# funcgen.net
KiCad netlist of a schematic drawn in Altium Designer
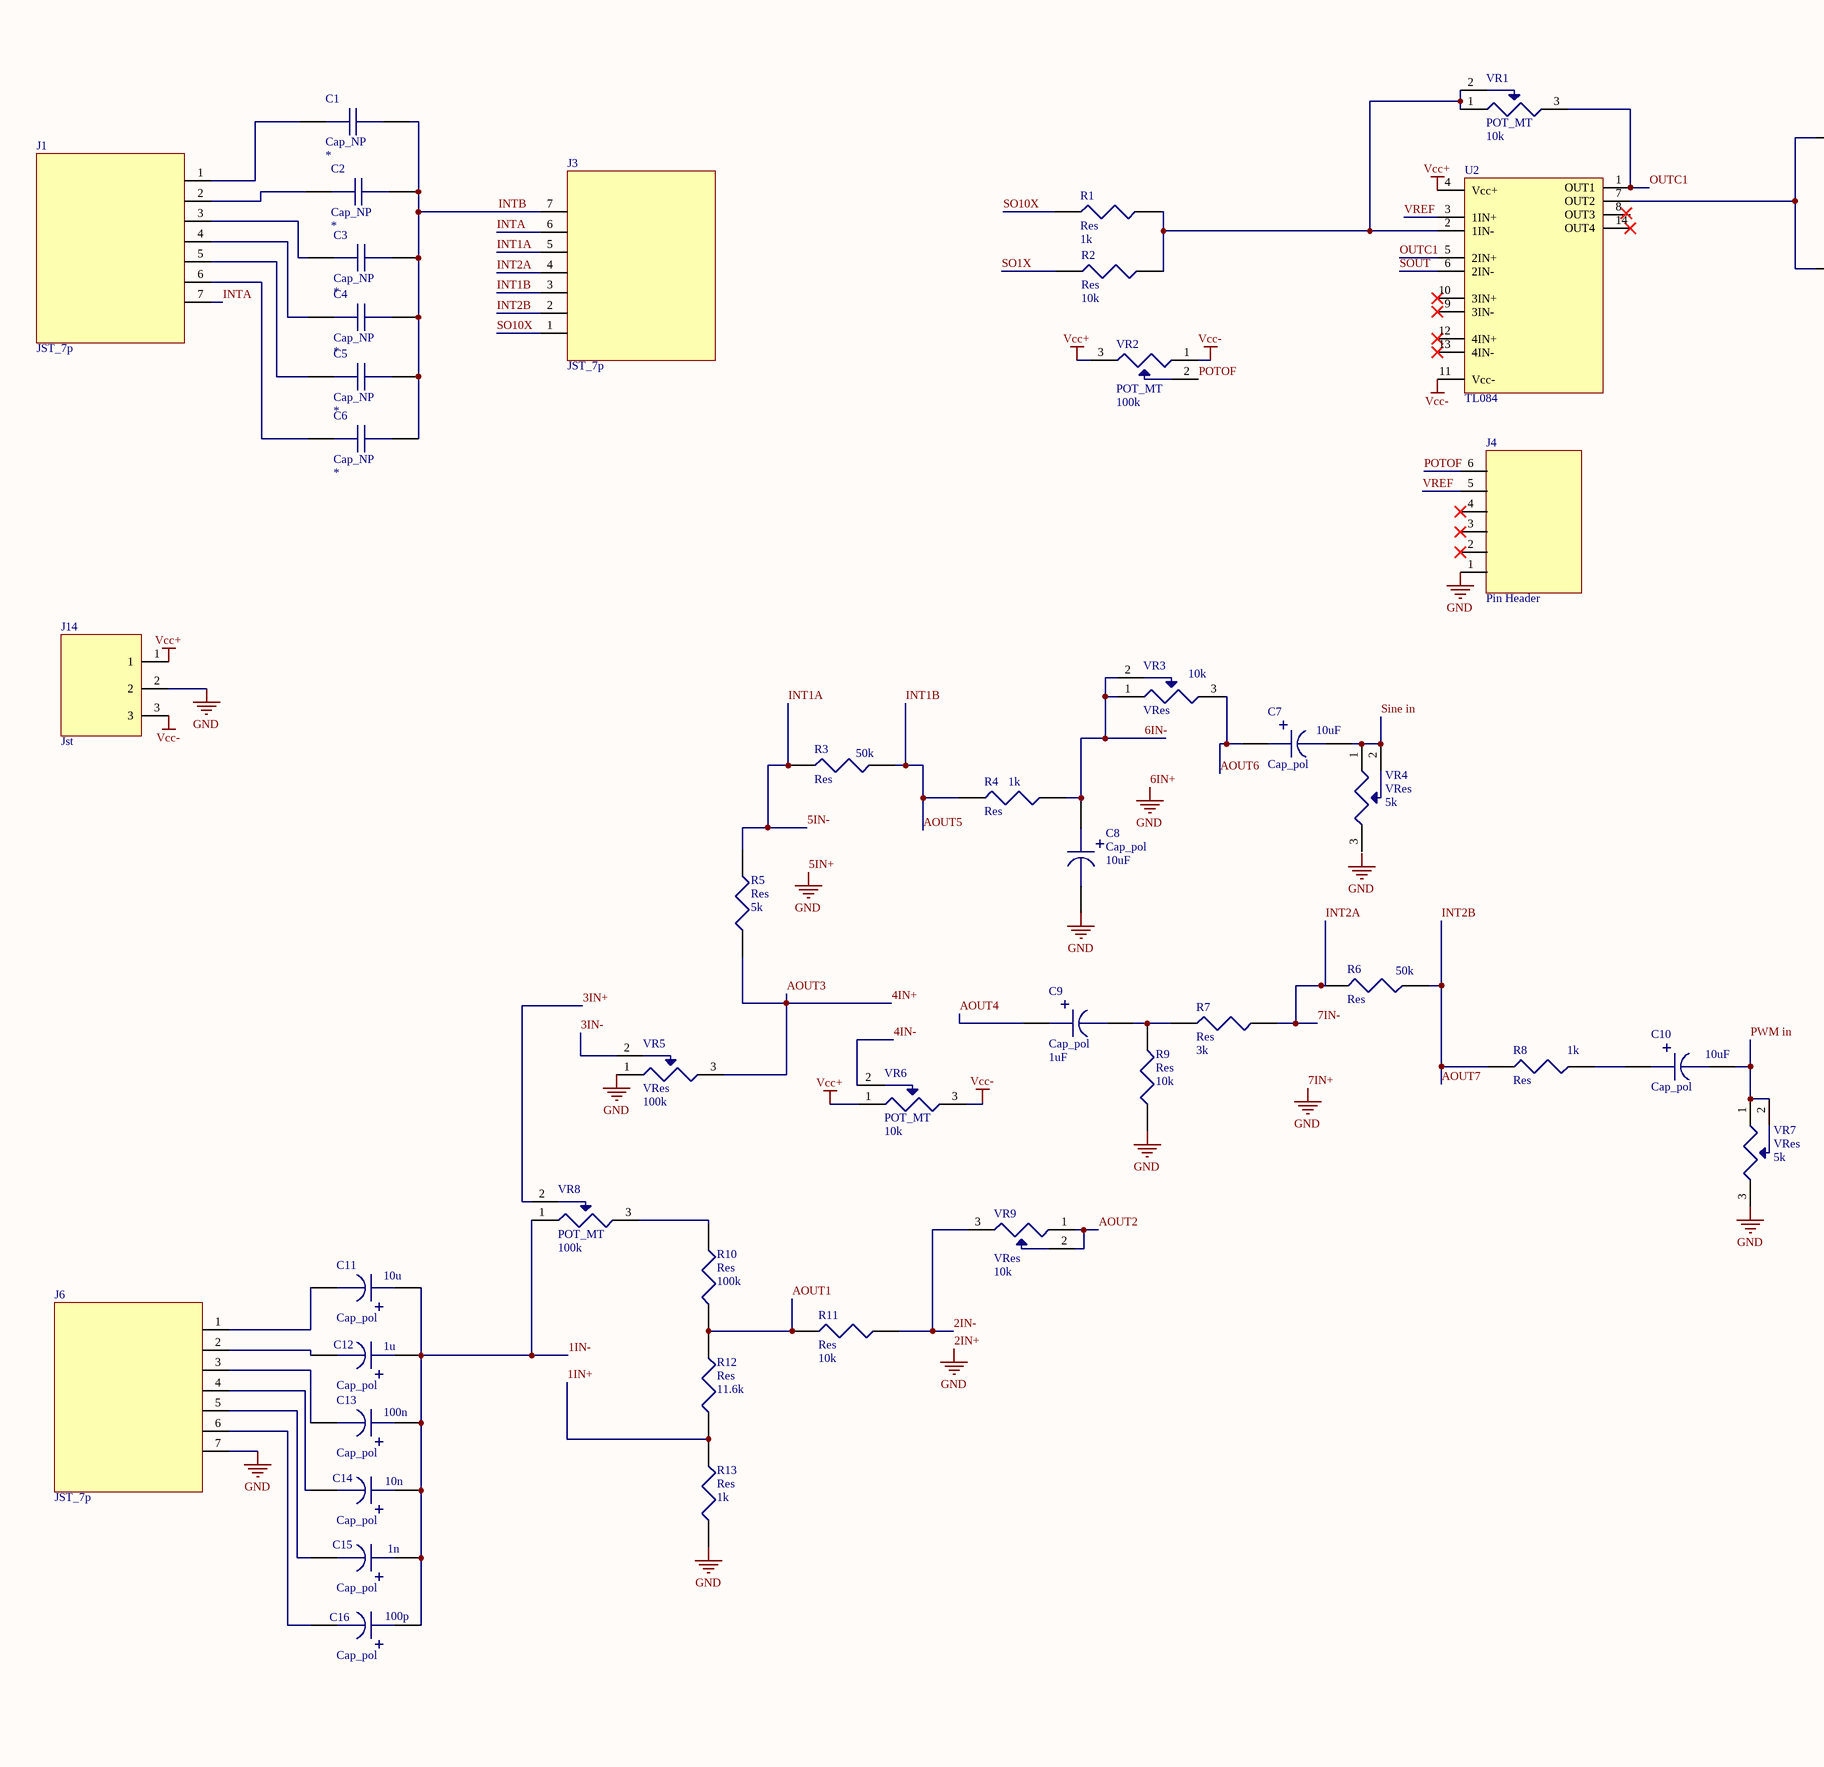
[diagram p0: funcgen.SchDoc, left]
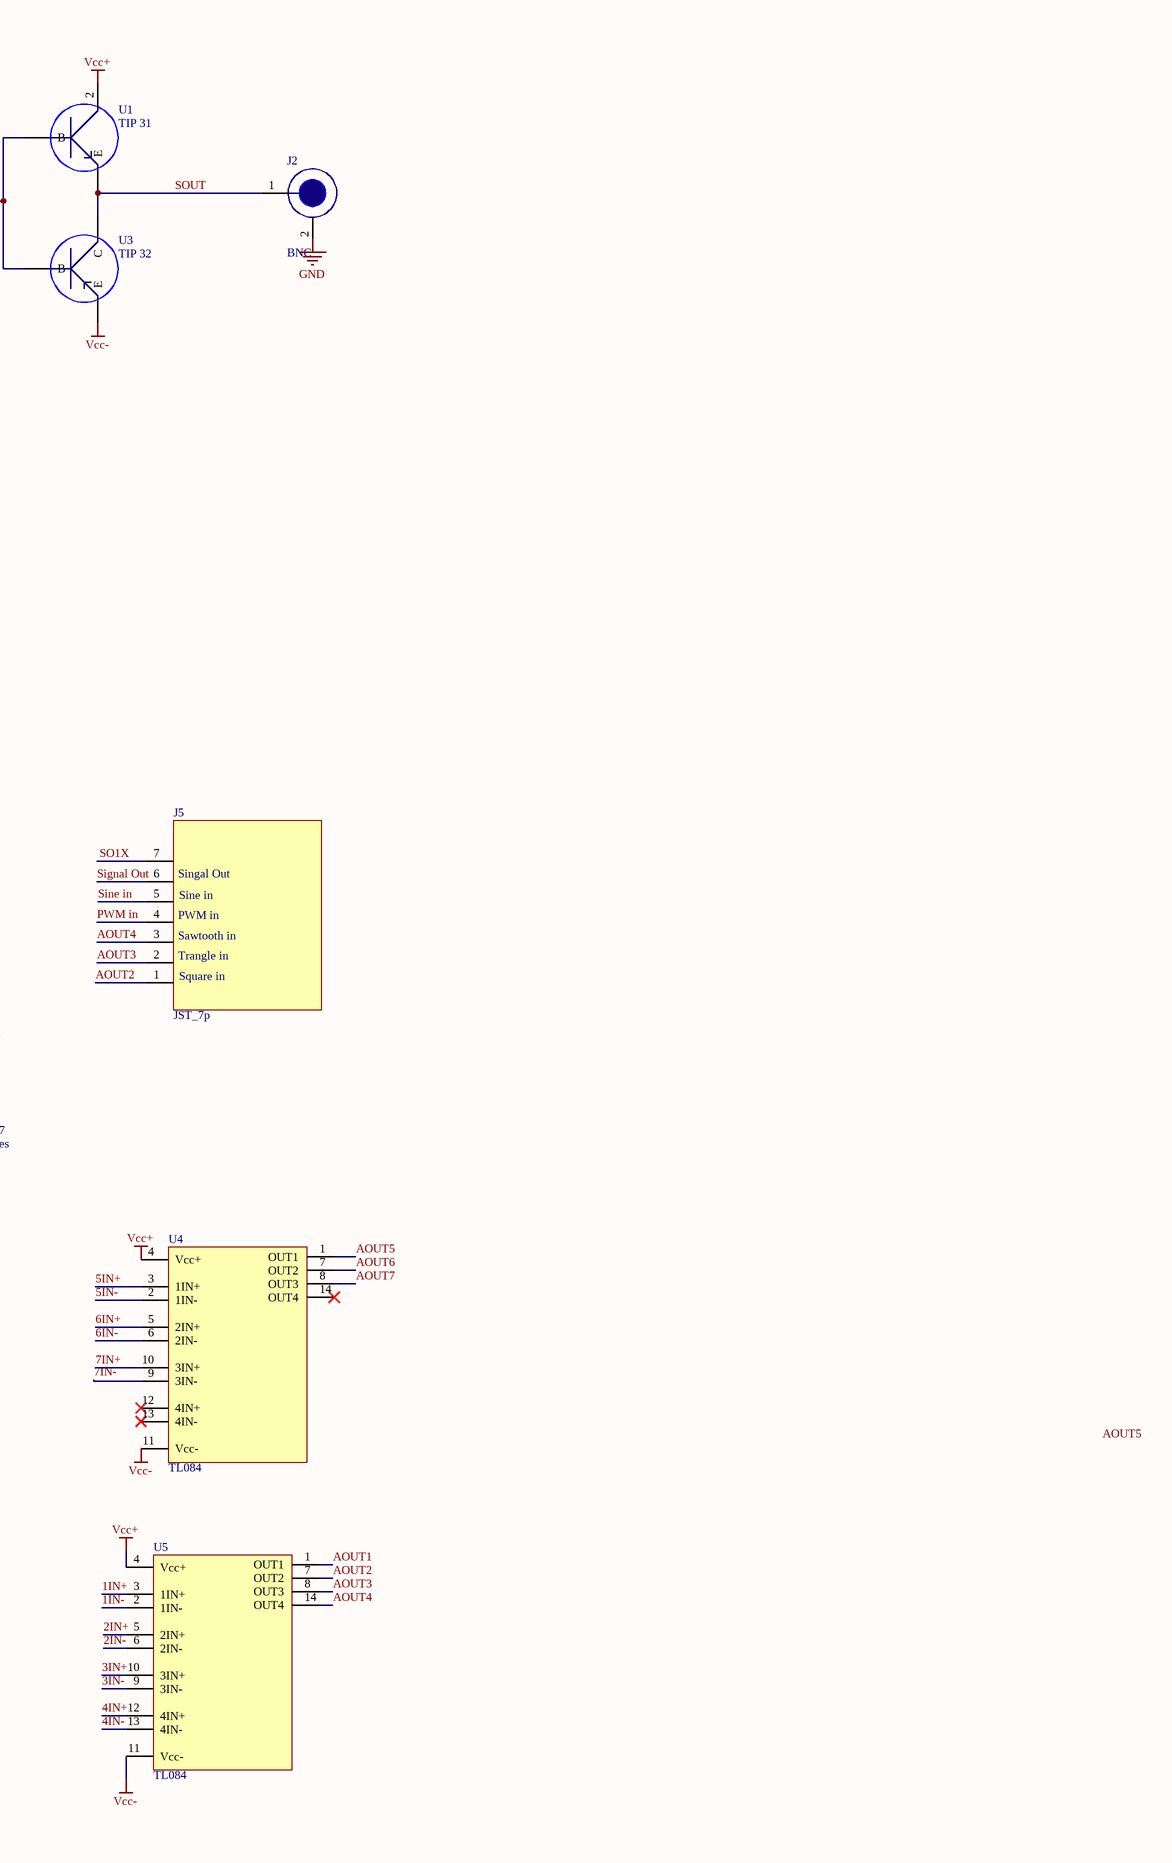
[diagram p1: funcgen.SchDoc, right]

(export (version "E")
  (design (tool "Eeschema 10.0.6"))
  (components
    (comp (ref "C1")
      (value "Cap_NP")
      (footprint "Cap NP")
      (fields (field (name "ALTIUM_VALUE") "*"))
      (libsource (lib "Funcgen") (part "Cap_NP"))
    )
    (comp (ref "C2")
      (value "Cap_NP")
      (footprint "Cap NP")
      (fields (field (name "ALTIUM_VALUE") "*"))
      (libsource (lib "Funcgen") (part "Cap_NP"))
    )
    (comp (ref "C3")
      (value "Cap_NP")
      (footprint "Cap NP")
      (fields (field (name "ALTIUM_VALUE") "*"))
      (libsource (lib "Funcgen") (part "Cap_NP"))
    )
    (comp (ref "C4")
      (value "Cap_NP")
      (footprint "Cap NP")
      (fields (field (name "ALTIUM_VALUE") "*"))
      (libsource (lib "Funcgen") (part "Cap_NP"))
    )
    (comp (ref "C5")
      (value "Cap_NP")
      (footprint "Cap NP")
      (fields (field (name "ALTIUM_VALUE") "*"))
      (libsource (lib "Funcgen") (part "Cap_NP"))
    )
    (comp (ref "C6")
      (value "Cap_NP")
      (footprint "Cap NP")
      (fields (field (name "ALTIUM_VALUE") "*"))
      (libsource (lib "Funcgen") (part "Cap_NP"))
    )
    (comp (ref "C7")
      (value "Cap_pol")
      (footprint "Cap pol")
      (fields (field (name "ALTIUM_VALUE") "10uF"))
      (libsource (lib "Schlib1") (part "Cap_pol"))
    )
    (comp (ref "C8")
      (value "Cap_pol")
      (footprint "Cap pol")
      (fields (field (name "ALTIUM_VALUE") "10uF"))
      (libsource (lib "Schlib1") (part "Cap_pol"))
    )
    (comp (ref "C9")
      (value "Cap_pol")
      (footprint "Cap pol")
      (fields (field (name "ALTIUM_VALUE") "1uF"))
      (libsource (lib "Schlib1") (part "Cap_pol"))
    )
    (comp (ref "C10")
      (value "Cap_pol")
      (footprint "Cap pol")
      (fields (field (name "ALTIUM_VALUE") "10uF"))
      (libsource (lib "Schlib1") (part "Cap_pol"))
    )
    (comp (ref "C11")
      (value "Cap_pol")
      (footprint "Cap pol")
      (fields (field (name "ALTIUM_VALUE") "10u"))
      (libsource (lib "Schlib1") (part "Cap_pol"))
    )
    (comp (ref "C12")
      (value "Cap_pol")
      (footprint "Cap pol")
      (fields (field (name "ALTIUM_VALUE") "1u"))
      (libsource (lib "Schlib1") (part "Cap_pol"))
    )
    (comp (ref "C13")
      (value "Cap_pol")
      (footprint "Cap pol")
      (fields (field (name "ALTIUM_VALUE") "100n"))
      (libsource (lib "Schlib1") (part "Cap_pol"))
    )
    (comp (ref "C14")
      (value "Cap_pol")
      (footprint "Cap pol")
      (fields (field (name "ALTIUM_VALUE") "10n"))
      (libsource (lib "Schlib1") (part "Cap_pol"))
    )
    (comp (ref "C15")
      (value "Cap_pol")
      (footprint "Cap pol")
      (fields (field (name "ALTIUM_VALUE") "1n"))
      (libsource (lib "Schlib1") (part "Cap_pol"))
    )
    (comp (ref "C16")
      (value "Cap_pol")
      (footprint "Cap pol")
      (fields (field (name "ALTIUM_VALUE") "100p"))
      (libsource (lib "Schlib1") (part "Cap_pol"))
    )
    (comp (ref "J1") (value "JST_7p") (footprint "JST_7p") (libsource (lib "Funcgen") (part "JST_7p")))
    (comp (ref "J2") (value "BNC") (footprint "PcbLib1:BNC") (libsource (lib "Funcgen") (part "BNC")))
    (comp (ref "J3") (value "JST_7p") (footprint "JST_7p") (libsource (lib "") (part "JST_7p_1")))
    (comp (ref "J4") (value "Pin Header") (footprint "JST_6p") (libsource (lib "Schlib1") (part "JST_6p")))
    (comp (ref "J5") (value "JST_7p") (footprint "JST_7p") (libsource (lib "") (part "JST_7p_1")))
    (comp (ref "J6") (value "JST_7p") (footprint "JST_7p") (libsource (lib "Funcgen") (part "JST_7p")))
    (comp (ref "J14") (value "Jst") (footprint "Funcgen:Jst_3p") (libsource (lib "Funcgen") (part "Jst_3p")))
    (comp (ref "R1")
      (value "Res")
      (footprint "Res")
      (fields (field (name "ALTIUM_VALUE") "1k"))
      (libsource (lib "Funcgen") (part "Res"))
    )
    (comp (ref "R2")
      (value "Res")
      (footprint "Res")
      (fields (field (name "ALTIUM_VALUE") "10k"))
      (libsource (lib "Funcgen") (part "Res"))
    )
    (comp (ref "R3")
      (value "Res")
      (footprint "Res")
      (fields (field (name "ALTIUM_VALUE") "50k"))
      (libsource (lib "Schlib1") (part "Res"))
    )
    (comp (ref "R4")
      (value "Res")
      (footprint "Res")
      (fields (field (name "ALTIUM_VALUE") "1k"))
      (libsource (lib "Schlib1") (part "Res"))
    )
    (comp (ref "R5")
      (value "Res")
      (footprint "Res")
      (fields (field (name "ALTIUM_VALUE") "5k"))
      (libsource (lib "Schlib1") (part "Res"))
    )
    (comp (ref "R6")
      (value "Res")
      (footprint "Res")
      (fields (field (name "ALTIUM_VALUE") "50k"))
      (libsource (lib "Schlib1") (part "Res"))
    )
    (comp (ref "R7")
      (value "Res")
      (footprint "Res")
      (fields (field (name "ALTIUM_VALUE") "3k"))
      (libsource (lib "Schlib1") (part "Res"))
    )
    (comp (ref "R8")
      (value "Res")
      (footprint "Res")
      (fields (field (name "ALTIUM_VALUE") "1k"))
      (libsource (lib "Schlib1") (part "Res"))
    )
    (comp (ref "R9")
      (value "Res")
      (footprint "Res")
      (fields (field (name "ALTIUM_VALUE") "10k"))
      (libsource (lib "Schlib1") (part "Res"))
    )
    (comp (ref "R10")
      (value "Res")
      (footprint "Res")
      (fields (field (name "ALTIUM_VALUE") "100k"))
      (libsource (lib "Schlib1") (part "Res"))
    )
    (comp (ref "R11")
      (value "Res")
      (footprint "Res")
      (fields (field (name "ALTIUM_VALUE") "10k"))
      (libsource (lib "Schlib1") (part "Res"))
    )
    (comp (ref "R12")
      (value "Res")
      (footprint "Res")
      (fields (field (name "ALTIUM_VALUE") "11.6k"))
      (libsource (lib "Schlib1") (part "Res"))
    )
    (comp (ref "R13")
      (value "Res")
      (footprint "Res")
      (fields (field (name "ALTIUM_VALUE") "1k"))
      (libsource (lib "Schlib1") (part "Res"))
    )
    (comp (ref "U1") (value "TIP 31") (footprint "TIP 31") (libsource (lib "Funcgen") (part "TIP 31")))
    (comp (ref "U2") (value "TL084") (footprint "TL084") (libsource (lib "Funcgen") (part "TL084")))
    (comp (ref "U3") (value "TIP 32") (footprint "TIP 31") (libsource (lib "Funcgen") (part "TIP 32")))
    (comp (ref "U4") (value "TL084") (footprint "TL084") (libsource (lib "Schlib1") (part "TL084")))
    (comp (ref "U5") (value "TL084") (footprint "TL084") (libsource (lib "Schlib1") (part "TL084")))
    (comp (ref "VR1")
      (value "POT_MT")
      (footprint "POT MT")
      (fields (field (name "ALTIUM_VALUE") "10k"))
      (libsource (lib "Funcgen") (part "POT_MT"))
    )
    (comp (ref "VR2")
      (value "POT_MT")
      (footprint "POT MT")
      (fields (field (name "ALTIUM_VALUE") "100k"))
      (libsource (lib "Funcgen") (part "POT_MT"))
    )
    (comp (ref "VR3")
      (value "VRes")
      (footprint "VerRes")
      (fields (field (name "ALTIUM_VALUE") "10k"))
      (libsource (lib "Schlib1") (part "VRes"))
    )
    (comp (ref "VR4")
      (value "VRes")
      (footprint "VerRes")
      (fields (field (name "ALTIUM_VALUE") "5k"))
      (libsource (lib "Schlib1") (part "VRes"))
    )
    (comp (ref "VR5")
      (value "VRes")
      (footprint "VerRes")
      (fields (field (name "ALTIUM_VALUE") "100k"))
      (libsource (lib "Schlib1") (part "VRes"))
    )
    (comp (ref "VR6")
      (value "POT_MT")
      (footprint "POT MT")
      (fields (field (name "ALTIUM_VALUE") "10k"))
      (libsource (lib "Schlib1") (part "POT_MT"))
    )
    (comp (ref "VR7")
      (value "VRes")
      (footprint "VerRes")
      (fields (field (name "ALTIUM_VALUE") "5k"))
      (libsource (lib "Schlib1") (part "VRes"))
    )
    (comp (ref "VR8")
      (value "POT_MT")
      (footprint "POT MT")
      (fields (field (name "ALTIUM_VALUE") "100k"))
      (libsource (lib "Schlib1") (part "POT_MT"))
    )
    (comp (ref "VR9")
      (value "VRes")
      (footprint "VerRes")
      (fields (field (name "ALTIUM_VALUE") "10k"))
      (libsource (lib "Schlib1") (part "VRes"))
    )
  )
  (nets
    (net (code "1") (name "/1IN+") (class "Default")
      (node (ref "R12") (pin "1") (pinfunction "1_1") (pintype "passive"))
      (node (ref "R13") (pin "2") (pinfunction "2_2") (pintype "passive"))
      (node (ref "U5") (pin "3") (pinfunction "1IN+_3") (pintype "passive"))
    )
    (net (code "2") (name "/1IN-") (class "Default")
      (node (ref "C11") (pin "1") (pinfunction "1_1") (pintype "passive"))
      (node (ref "C12") (pin "1") (pinfunction "1_1") (pintype "passive"))
      (node (ref "C13") (pin "1") (pinfunction "1_1") (pintype "passive"))
      (node (ref "C14") (pin "1") (pinfunction "1_1") (pintype "passive"))
      (node (ref "C15") (pin "1") (pinfunction "1_1") (pintype "passive"))
      (node (ref "C16") (pin "1") (pinfunction "1_1") (pintype "passive"))
      (node (ref "U5") (pin "2") (pinfunction "1IN-_2") (pintype "passive"))
      (node (ref "VR8") (pin "1") (pinfunction "1_1") (pintype "passive"))
    )
    (net (code "3") (name "/2IN-") (class "Default")
      (node (ref "R11") (pin "2") (pinfunction "2_2") (pintype "passive"))
      (node (ref "U5") (pin "6") (pinfunction "2IN-_6") (pintype "passive"))
      (node (ref "VR9") (pin "3") (pinfunction "3_3") (pintype "passive"))
    )
    (net (code "4") (name "/3IN+") (class "Default")
      (node (ref "U5") (pin "10") (pinfunction "3IN+_10") (pintype "passive"))
      (node (ref "VR8") (pin "2") (pinfunction "2_2") (pintype "passive"))
    )
    (net (code "5") (name "/3IN-") (class "Default")
      (node (ref "U5") (pin "9") (pinfunction "3IN-_9") (pintype "passive"))
      (node (ref "VR5") (pin "2") (pinfunction "2_2") (pintype "passive"))
    )
    (net (code "6") (name "/4IN+") (class "Default")
      (node (ref "J5") (pin "2") (pinfunction "2_2") (pintype "passive"))
      (node (ref "R5") (pin "1") (pinfunction "1_1") (pintype "passive"))
      (node (ref "U5") (pin "12") (pinfunction "4IN+_12") (pintype "passive"))
      (node (ref "U5") (pin "8") (pinfunction "OUT3_8") (pintype "passive"))
      (node (ref "VR5") (pin "3") (pinfunction "3_3") (pintype "passive"))
    )
    (net (code "7") (name "/4IN-") (class "Default")
      (node (ref "U5") (pin "13") (pinfunction "4IN-_13") (pintype "passive"))
      (node (ref "VR6") (pin "2") (pinfunction "2_2") (pintype "passive"))
    )
    (net (code "8") (name "/5IN-") (class "Default")
      (node (ref "J3") (pin "5") (pinfunction "5_5") (pintype "passive"))
      (node (ref "R3") (pin "1") (pinfunction "1_1") (pintype "passive"))
      (node (ref "R5") (pin "2") (pinfunction "2_2") (pintype "passive"))
      (node (ref "U4") (pin "2") (pinfunction "1IN-_2") (pintype "passive"))
    )
    (net (code "9") (name "/6IN-") (class "Default")
      (node (ref "C8") (pin "1") (pinfunction "1_1") (pintype "passive"))
      (node (ref "R4") (pin "2") (pinfunction "2_2") (pintype "passive"))
      (node (ref "U4") (pin "6") (pinfunction "2IN-_6") (pintype "passive"))
      (node (ref "VR3") (pin "1") (pinfunction "1_1") (pintype "passive"))
      (node (ref "VR3") (pin "2") (pinfunction "2_2") (pintype "passive"))
    )
    (net (code "10") (name "/7IN-") (class "Default")
      (node (ref "J3") (pin "4") (pinfunction "4_4") (pintype "passive"))
      (node (ref "R6") (pin "2") (pinfunction "2_2") (pintype "passive"))
      (node (ref "R7") (pin "1") (pinfunction "1_1") (pintype "passive"))
      (node (ref "U4") (pin "9") (pinfunction "3IN-_9") (pintype "passive"))
    )
    (net (code "11") (name "/AOUT1") (class "Default")
      (node (ref "R10") (pin "2") (pinfunction "2_2") (pintype "passive"))
      (node (ref "R11") (pin "1") (pinfunction "1_1") (pintype "passive"))
      (node (ref "R12") (pin "2") (pinfunction "2_2") (pintype "passive"))
      (node (ref "U5") (pin "1") (pinfunction "OUT1_1") (pintype "passive"))
    )
    (net (code "12") (name "/AOUT2") (class "Default")
      (node (ref "J5") (pin "1") (pinfunction "1_1") (pintype "passive"))
      (node (ref "U5") (pin "7") (pinfunction "OUT2_7") (pintype "passive"))
      (node (ref "VR9") (pin "1") (pinfunction "1_1") (pintype "passive"))
      (node (ref "VR9") (pin "2") (pinfunction "2_2") (pintype "passive"))
    )
    (net (code "13") (name "/AOUT4") (class "Default")
      (node (ref "C9") (pin "1") (pinfunction "1_1") (pintype "passive"))
      (node (ref "J5") (pin "3") (pinfunction "3_3") (pintype "passive"))
      (node (ref "U5") (pin "14") (pinfunction "OUT4_14") (pintype "passive"))
    )
    (net (code "14") (name "/AOUT5") (class "Default")
      (node (ref "J3") (pin "3") (pinfunction "3_3") (pintype "passive"))
      (node (ref "R3") (pin "2") (pinfunction "2_2") (pintype "passive"))
      (node (ref "R4") (pin "1") (pinfunction "1_1") (pintype "passive"))
      (node (ref "U4") (pin "1") (pinfunction "OUT1_1") (pintype "passive"))
    )
    (net (code "15") (name "/AOUT6") (class "Default")
      (node (ref "C7") (pin "1") (pinfunction "1_1") (pintype "passive"))
      (node (ref "U4") (pin "7") (pinfunction "OUT2_7") (pintype "passive"))
      (node (ref "VR3") (pin "3") (pinfunction "3_3") (pintype "passive"))
    )
    (net (code "16") (name "/AOUT7") (class "Default")
      (node (ref "J3") (pin "2") (pinfunction "2_2") (pintype "passive"))
      (node (ref "R6") (pin "1") (pinfunction "1_1") (pintype "passive"))
      (node (ref "R8") (pin "1") (pinfunction "1_1") (pintype "passive"))
      (node (ref "U4") (pin "8") (pinfunction "OUT3_8") (pintype "passive"))
    )
    (net (code "17") (name "/INTA") (class "Default")
      (node (ref "J1") (pin "7") (pinfunction "7_7") (pintype "passive"))
      (node (ref "J3") (pin "6") (pinfunction "6_6") (pintype "passive"))
    )
    (net (code "18") (name "/INTB") (class "Default")
      (node (ref "C1") (pin "2") (pinfunction "2_2") (pintype "passive"))
      (node (ref "C2") (pin "2") (pinfunction "2_2") (pintype "passive"))
      (node (ref "C3") (pin "2") (pinfunction "2_2") (pintype "passive"))
      (node (ref "C4") (pin "2") (pinfunction "2_2") (pintype "passive"))
      (node (ref "C5") (pin "2") (pinfunction "2_2") (pintype "passive"))
      (node (ref "C6") (pin "2") (pinfunction "2_2") (pintype "passive"))
      (node (ref "J3") (pin "7") (pinfunction "7_7") (pintype "passive"))
    )
    (net (code "19") (name "/OUTC1") (class "Default")
      (node (ref "U2") (pin "1") (pinfunction "OUT1_1") (pintype "passive"))
      (node (ref "U2") (pin "5") (pinfunction "2IN+_5") (pintype "passive"))
      (node (ref "VR1") (pin "3") (pinfunction "3_3") (pintype "passive"))
    )
    (net (code "20") (name "/POTOF") (class "Default")
      (node (ref "J4") (pin "6") (pinfunction "6_6") (pintype "passive"))
      (node (ref "VR2") (pin "2") (pinfunction "2_2") (pintype "passive"))
    )
    (net (code "21") (name "/PWM in") (class "Default")
      (node (ref "C10") (pin "2") (pinfunction "2_2") (pintype "passive"))
      (node (ref "J5") (pin "4") (pinfunction "4_4") (pintype "passive"))
      (node (ref "VR7") (pin "1") (pinfunction "1_1") (pintype "passive"))
      (node (ref "VR7") (pin "2") (pinfunction "2_2") (pintype "passive"))
    )
    (net (code "22") (name "/SO1X") (class "Default")
      (node (ref "J5") (pin "7") (pinfunction "7_7") (pintype "passive"))
      (node (ref "R2") (pin "1") (pinfunction "1_1") (pintype "passive"))
    )
    (net (code "23") (name "/SO10X") (class "Default")
      (node (ref "J3") (pin "1") (pinfunction "1_1") (pintype "passive"))
      (node (ref "R1") (pin "1") (pinfunction "1_1") (pintype "passive"))
    )
    (net (code "24") (name "/SOUT") (class "Default")
      (node (ref "J2") (pin "1") (pinfunction "1_1") (pintype "passive"))
      (node (ref "U1") (pin "3") (pinfunction "E_3") (pintype "passive"))
      (node (ref "U2") (pin "6") (pinfunction "2IN-_6") (pintype "passive"))
      (node (ref "U3") (pin "2") (pinfunction "C_2") (pintype "passive"))
    )
    (net (code "25") (name "/Signal Out") (class "Default")
      (node (ref "J5") (pin "6") (pinfunction "6_6") (pintype "passive"))
    )
    (net (code "26") (name "/Sine in") (class "Default")
      (node (ref "C7") (pin "2") (pinfunction "2_2") (pintype "passive"))
      (node (ref "J5") (pin "5") (pinfunction "5_5") (pintype "passive"))
      (node (ref "VR4") (pin "1") (pinfunction "1_1") (pintype "passive"))
      (node (ref "VR4") (pin "2") (pinfunction "2_2") (pintype "passive"))
    )
    (net (code "27") (name "/VREF") (class "Default")
      (node (ref "J4") (pin "5") (pinfunction "5_5") (pintype "passive"))
      (node (ref "U2") (pin "3") (pinfunction "1IN+_3") (pintype "passive"))
    )
    (net (code "28") (name "GND") (class "Default")
      (node (ref "C8") (pin "2") (pinfunction "2_2") (pintype "passive"))
      (node (ref "J14") (pin "2") (pinfunction "2_2") (pintype "passive"))
      (node (ref "J4") (pin "1") (pinfunction "1_1") (pintype "passive"))
      (node (ref "J6") (pin "7") (pinfunction "7_7") (pintype "passive"))
      (node (ref "R13") (pin "1") (pinfunction "1_1") (pintype "passive"))
      (node (ref "R9") (pin "1") (pinfunction "1_1") (pintype "passive"))
      (node (ref "U4") (pin "10") (pinfunction "3IN+_10") (pintype "passive"))
      (node (ref "U4") (pin "3") (pinfunction "1IN+_3") (pintype "passive"))
      (node (ref "U4") (pin "5") (pinfunction "2IN+_5") (pintype "passive"))
      (node (ref "U5") (pin "5") (pinfunction "2IN+_5") (pintype "passive"))
      (node (ref "VR5") (pin "1") (pinfunction "1_1") (pintype "passive"))
      (node (ref "VR7") (pin "3") (pinfunction "3_3") (pintype "passive"))
    )
    (net (code "29") (name "Net-(C1-Pad1)") (class "Default")
      (node (ref "C1") (pin "1") (pinfunction "1_1") (pintype "passive"))
      (node (ref "J1") (pin "1") (pinfunction "1_1") (pintype "passive"))
    )
    (net (code "30") (name "Net-(C2-Pad1)") (class "Default")
      (node (ref "C2") (pin "1") (pinfunction "1_1") (pintype "passive"))
      (node (ref "J1") (pin "2") (pinfunction "2_2") (pintype "passive"))
    )
    (net (code "31") (name "Net-(C3-Pad1)") (class "Default")
      (node (ref "C3") (pin "1") (pinfunction "1_1") (pintype "passive"))
      (node (ref "J1") (pin "3") (pinfunction "3_3") (pintype "passive"))
    )
    (net (code "32") (name "Net-(C4-Pad1)") (class "Default")
      (node (ref "C4") (pin "1") (pinfunction "1_1") (pintype "passive"))
      (node (ref "J1") (pin "4") (pinfunction "4_4") (pintype "passive"))
    )
    (net (code "33") (name "Net-(C5-Pad1)") (class "Default")
      (node (ref "C5") (pin "1") (pinfunction "1_1") (pintype "passive"))
      (node (ref "J1") (pin "5") (pinfunction "5_5") (pintype "passive"))
    )
    (net (code "34") (name "Net-(C6-Pad1)") (class "Default")
      (node (ref "C6") (pin "1") (pinfunction "1_1") (pintype "passive"))
      (node (ref "J1") (pin "6") (pinfunction "6_6") (pintype "passive"))
    )
    (net (code "35") (name "Net-(C9-Pad2)") (class "Default")
      (node (ref "C9") (pin "2") (pinfunction "2_2") (pintype "passive"))
      (node (ref "R7") (pin "2") (pinfunction "2_2") (pintype "passive"))
      (node (ref "R9") (pin "2") (pinfunction "2_2") (pintype "passive"))
    )
    (net (code "36") (name "Net-(C10-Pad1)") (class "Default")
      (node (ref "C10") (pin "1") (pinfunction "1_1") (pintype "passive"))
      (node (ref "R8") (pin "2") (pinfunction "2_2") (pintype "passive"))
    )
    (net (code "37") (name "Net-(C11-Pad2)") (class "Default")
      (node (ref "C11") (pin "2") (pinfunction "2_2") (pintype "passive"))
      (node (ref "J6") (pin "1") (pinfunction "1_1") (pintype "passive"))
    )
    (net (code "38") (name "Net-(C12-Pad2)") (class "Default")
      (node (ref "C12") (pin "2") (pinfunction "2_2") (pintype "passive"))
      (node (ref "J6") (pin "2") (pinfunction "2_2") (pintype "passive"))
    )
    (net (code "39") (name "Net-(C13-Pad2)") (class "Default")
      (node (ref "C13") (pin "2") (pinfunction "2_2") (pintype "passive"))
      (node (ref "J6") (pin "3") (pinfunction "3_3") (pintype "passive"))
    )
    (net (code "40") (name "Net-(C14-Pad2)") (class "Default")
      (node (ref "C14") (pin "2") (pinfunction "2_2") (pintype "passive"))
      (node (ref "J6") (pin "4") (pinfunction "4_4") (pintype "passive"))
    )
    (net (code "41") (name "Net-(C15-Pad2)") (class "Default")
      (node (ref "C15") (pin "2") (pinfunction "2_2") (pintype "passive"))
      (node (ref "J6") (pin "5") (pinfunction "5_5") (pintype "passive"))
    )
    (net (code "42") (name "Net-(C16-Pad2)") (class "Default")
      (node (ref "C16") (pin "2") (pinfunction "2_2") (pintype "passive"))
      (node (ref "J6") (pin "6") (pinfunction "6_6") (pintype "passive"))
    )
    (net (code "43") (name "Net-(R10-Pad1)") (class "Default")
      (node (ref "R10") (pin "1") (pinfunction "1_1") (pintype "passive"))
      (node (ref "VR8") (pin "3") (pinfunction "3_3") (pintype "passive"))
    )
    (net (code "44") (name "Net-(U1-B)") (class "Default")
      (node (ref "U1") (pin "1") (pinfunction "B_1") (pintype "passive"))
      (node (ref "U2") (pin "7") (pinfunction "OUT2_7") (pintype "passive"))
      (node (ref "U3") (pin "1") (pinfunction "B_1") (pintype "passive"))
    )
    (net (code "45") (name "Net-(U2-1IN-)") (class "Default")
      (node (ref "R1") (pin "2") (pinfunction "2_2") (pintype "passive"))
      (node (ref "R2") (pin "2") (pinfunction "2_2") (pintype "passive"))
      (node (ref "U2") (pin "2") (pinfunction "1IN-_2") (pintype "passive"))
      (node (ref "VR1") (pin "1") (pinfunction "1_1") (pintype "passive"))
      (node (ref "VR1") (pin "2") (pinfunction "2_2") (pintype "passive"))
    )
    (net (code "46") (name "Vcc+") (class "Default")
      (node (ref "J14") (pin "1") (pinfunction "1_1") (pintype "passive"))
      (node (ref "U1") (pin "2") (pinfunction "3_2") (pintype "passive"))
      (node (ref "U2") (pin "4") (pinfunction "Vcc+_4") (pintype "passive"))
      (node (ref "U4") (pin "4") (pinfunction "Vcc+_4") (pintype "passive"))
      (node (ref "U5") (pin "4") (pinfunction "Vcc+_4") (pintype "passive"))
      (node (ref "VR2") (pin "3") (pinfunction "3_3") (pintype "passive"))
      (node (ref "VR6") (pin "1") (pinfunction "1_1") (pintype "passive"))
    )
    (net (code "47") (name "Vcc-") (class "Default")
      (node (ref "J14") (pin "3") (pinfunction "3_3") (pintype "passive"))
      (node (ref "U2") (pin "11") (pinfunction "Vcc-_11") (pintype "passive"))
      (node (ref "U3") (pin "3") (pinfunction "E_3") (pintype "passive"))
      (node (ref "U4") (pin "11") (pinfunction "Vcc-_11") (pintype "passive"))
      (node (ref "U5") (pin "11") (pinfunction "Vcc-_11") (pintype "passive"))
      (node (ref "VR2") (pin "1") (pinfunction "1_1") (pintype "passive"))
      (node (ref "VR6") (pin "3") (pinfunction "3_3") (pintype "passive"))
    )
    (net (code "48") (name "unconnected-(J2-Pad2)") (class "Default")
      (node (ref "J2") (pin "2") (pinfunction "2_2") (pintype "passive"))
    )
    (net (code "49") (name "unconnected-(J4-Pad2)") (class "Default")
      (node (ref "J4") (pin "2") (pinfunction "2_2") (pintype "passive+no_connect"))
    )
    (net (code "50") (name "unconnected-(J4-Pad3)") (class "Default")
      (node (ref "J4") (pin "3") (pinfunction "3_3") (pintype "passive+no_connect"))
    )
    (net (code "51") (name "unconnected-(J4-Pad4)") (class "Default")
      (node (ref "J4") (pin "4") (pinfunction "4_4") (pintype "passive+no_connect"))
    )
    (net (code "52") (name "unconnected-(U2-3IN+-Pad10)") (class "Default")
      (node (ref "U2") (pin "10") (pinfunction "3IN+_10") (pintype "passive+no_connect"))
    )
    (net (code "53") (name "unconnected-(U2-3IN--Pad9)") (class "Default")
      (node (ref "U2") (pin "9") (pinfunction "3IN-_9") (pintype "passive+no_connect"))
    )
    (net (code "54") (name "unconnected-(U2-4IN+-Pad12)") (class "Default")
      (node (ref "U2") (pin "12") (pinfunction "4IN+_12") (pintype "passive+no_connect"))
    )
    (net (code "55") (name "unconnected-(U2-4IN--Pad13)") (class "Default")
      (node (ref "U2") (pin "13") (pinfunction "4IN-_13") (pintype "passive+no_connect"))
    )
    (net (code "56") (name "unconnected-(U2-OUT3-Pad8)") (class "Default")
      (node (ref "U2") (pin "8") (pinfunction "OUT3_8") (pintype "passive"))
    )
    (net (code "57") (name "unconnected-(U2-OUT4-Pad14)") (class "Default")
      (node (ref "U2") (pin "14") (pinfunction "OUT4_14") (pintype "passive+no_connect"))
    )
    (net (code "58") (name "unconnected-(U4-4IN+-Pad12)") (class "Default")
      (node (ref "U4") (pin "12") (pinfunction "4IN+_12") (pintype "passive+no_connect"))
    )
    (net (code "59") (name "unconnected-(U4-4IN--Pad13)") (class "Default")
      (node (ref "U4") (pin "13") (pinfunction "4IN-_13") (pintype "passive+no_connect"))
    )
    (net (code "60") (name "unconnected-(U4-OUT4-Pad14)") (class "Default")
      (node (ref "U4") (pin "14") (pinfunction "OUT4_14") (pintype "passive+no_connect"))
    )
    (net (code "61") (name "unconnected-(VR4-Pad3)") (class "Default")
      (node (ref "VR4") (pin "3") (pinfunction "3_3") (pintype "passive"))
    )
  )
)
